# Net.net
KiCad netlist of a schematic drawn in Altium Designer
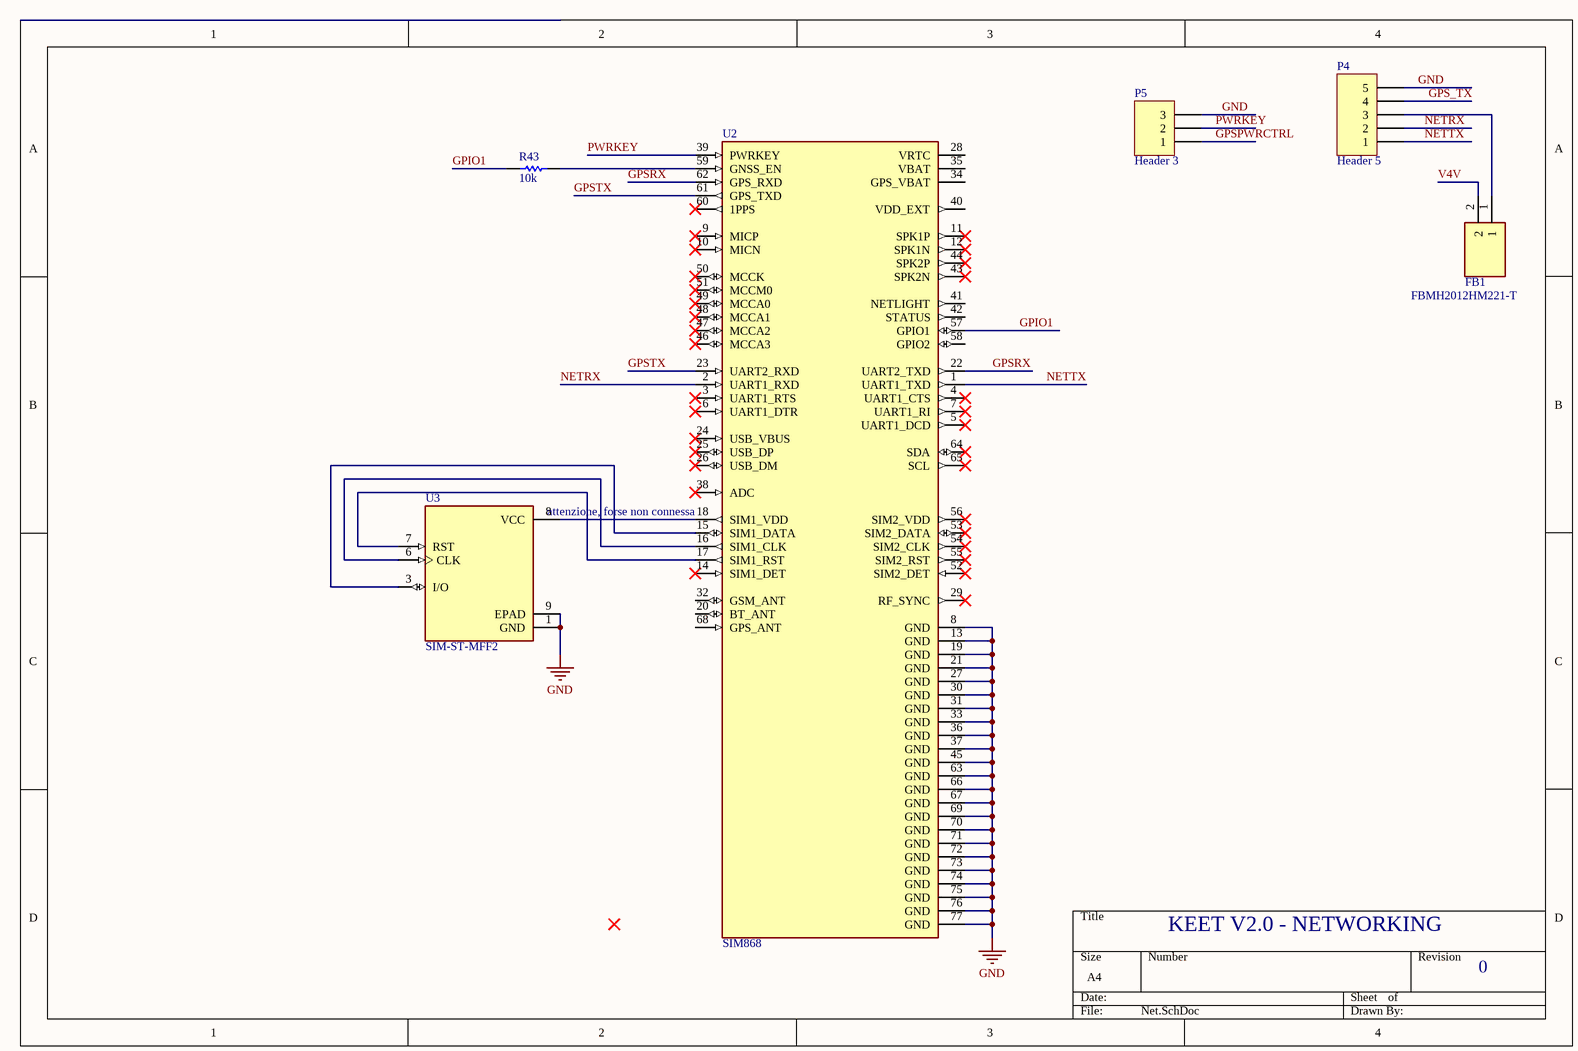
[diagram p0: Net.SchDoc]

(export (version "E")
  (design (tool "Eeschema 10.0.6"))
  (components
    (comp (ref "FB1")
      (value "FBMH2012HM221-T")
      (footprint "SamacSys:BEADC2012X105N")
      (description "Ferrite Bead")
      (fields (field (name "MOUSER PART NUMBER") "963-FBMH2012HM221-T"))
      (libsource (lib "*") (part "FBMH2012HM221-T"))
    )
    (comp (ref "P4")
      (value "Header 5")
      (footprint "HDR1X5")
      (description "Header, 5-Pin")
      (fields (field (name "PUBLISHER") "Altium Limited"))
      (libsource (lib "Miscellaneous Connectors") (part "Header 5"))
    )
    (comp (ref "P5")
      (value "Header 3")
      (footprint "HDR1X3")
      (description "Header, 3-Pin")
      (fields (field (name "PUBLISHER") "Altium Limited"))
      (libsource (lib "Miscellaneous Connectors") (part "Header 3"))
    )
    (comp (ref "R43")
      (value "10k")
      (footprint "RESC1005X04N")
      (description "Res Thick Film 0402 10K Ohm 1% 1/16W ±100ppm/°C Molded SMD Paper T/R")
      (fields
        (field (name "MANUFACTURER") "Vishay")
        (field (name "MANUFACTURER PART NUMBER") "CRCW0402-10K0FKED")
      )
      (libsource (lib "KeetV2") (part "CRCW0402-10K0FKED"))
    )
    (comp (ref "U2")
      (value "SIM868")
      (footprint "XCVR_SIM868")
      (description "SIM868 GNSS, GSM RF mikroBUSâ„¢ Clickâ„¢ Platform Evaluation Expansion Board")
      (fields (field (name "MF") "MikroElektronika"))
      (libsource (lib "SIM868") (part "SIM868"))
    )
    (comp (ref "U3")
      (value "SIM-ST-MFF2")
      (footprint "PSON127P500X600X82-9N")
      (description "GLOBAL IOT EMBEDDED SIM CHIP")
      (fields (field (name "MF") "Hologram, Inc."))
      (libsource (lib "SIM-ST-MFF2") (part "SIM-ST-MFF2"))
    )
  )
  (nets
    (net (code "1") (name "/GPIO1") (class "Default")
      (node (ref "R43") (pin "2") (pinfunction "2_2") (pintype "passive"))
      (node (ref "U2") (pin "57") (pinfunction "GPIO1_57") (pintype "bidirectional"))
    )
    (net (code "2") (name "/GPSPWRCTRL") (class "Default")
      (node (ref "P5") (pin "1") (pinfunction "1_1") (pintype "passive"))
    )
    (net (code "3") (name "/GPSRX") (class "Default")
      (node (ref "U2") (pin "22") (pinfunction "UART2_TXD_22") (pintype "output"))
      (node (ref "U2") (pin "62") (pinfunction "GPS_RXD_62") (pintype "input"))
    )
    (net (code "4") (name "/GPSTX") (class "Default")
      (node (ref "U2") (pin "23") (pinfunction "UART2_RXD_23") (pintype "input"))
      (node (ref "U2") (pin "61") (pinfunction "GPS_TXD_61") (pintype "output"))
    )
    (net (code "5") (name "/GPS_TX") (class "Default")
      (node (ref "P4") (pin "4") (pinfunction "4_4") (pintype "passive"))
    )
    (net (code "6") (name "/NETRX") (class "Default")
      (node (ref "P4") (pin "2") (pinfunction "2_2") (pintype "passive"))
      (node (ref "U2") (pin "2") (pinfunction "UART1_RXD_2") (pintype "input"))
    )
    (net (code "7") (name "/NETTX") (class "Default")
      (node (ref "P4") (pin "1") (pinfunction "1_1") (pintype "passive"))
      (node (ref "U2") (pin "1") (pinfunction "UART1_TXD_1") (pintype "output"))
    )
    (net (code "8") (name "/PWRKEY") (class "Default")
      (node (ref "P5") (pin "2") (pinfunction "2_2") (pintype "passive"))
      (node (ref "U2") (pin "39") (pinfunction "PWRKEY_39") (pintype "input"))
    )
    (net (code "9") (name "/V4V") (class "Default")
      (node (ref "FB1") (pin "2") (pinfunction "2_2") (pintype "passive"))
    )
    (net (code "10") (name "GND") (class "Default")
      (node (ref "P4") (pin "5") (pinfunction "5_5") (pintype "passive"))
      (node (ref "P5") (pin "3") (pinfunction "3_3") (pintype "passive"))
      (node (ref "U2") (pin "13") (pinfunction "GND_13") (pintype "power_in"))
      (node (ref "U2") (pin "19") (pinfunction "GND_19") (pintype "power_in"))
      (node (ref "U2") (pin "21") (pinfunction "GND_21") (pintype "power_in"))
      (node (ref "U2") (pin "27") (pinfunction "GND_27") (pintype "power_in"))
      (node (ref "U2") (pin "30") (pinfunction "GND_30") (pintype "power_in"))
      (node (ref "U2") (pin "31") (pinfunction "GND_31") (pintype "power_in"))
      (node (ref "U2") (pin "33") (pinfunction "GND_33") (pintype "power_in"))
      (node (ref "U2") (pin "36") (pinfunction "GND_36") (pintype "power_in"))
      (node (ref "U2") (pin "37") (pinfunction "GND_37") (pintype "power_in"))
      (node (ref "U2") (pin "45") (pinfunction "GND_45") (pintype "power_in"))
      (node (ref "U2") (pin "63") (pinfunction "GND_63") (pintype "power_in"))
      (node (ref "U2") (pin "66") (pinfunction "GND_66") (pintype "power_in"))
      (node (ref "U2") (pin "67") (pinfunction "GND_67") (pintype "power_in"))
      (node (ref "U2") (pin "69") (pinfunction "GND_69") (pintype "power_in"))
      (node (ref "U2") (pin "70") (pinfunction "GND_70") (pintype "power_in"))
      (node (ref "U2") (pin "71") (pinfunction "GND_71") (pintype "power_in"))
      (node (ref "U2") (pin "72") (pinfunction "GND_72") (pintype "power_in"))
      (node (ref "U2") (pin "73") (pinfunction "GND_73") (pintype "power_in"))
      (node (ref "U2") (pin "74") (pinfunction "GND_74") (pintype "power_in"))
      (node (ref "U2") (pin "75") (pinfunction "GND_75") (pintype "power_in"))
      (node (ref "U2") (pin "76") (pinfunction "GND_76") (pintype "power_in"))
      (node (ref "U2") (pin "77") (pinfunction "GND_77") (pintype "power_in"))
      (node (ref "U2") (pin "8") (pinfunction "GND_8") (pintype "power_in"))
      (node (ref "U3") (pin "1") (pinfunction "GND_1") (pintype "power_in"))
      (node (ref "U3") (pin "9") (pinfunction "EPAD_9") (pintype "passive"))
    )
    (net (code "11") (name "Net-(FB1-Pad1)") (class "Default")
      (node (ref "FB1") (pin "1") (pinfunction "1_1") (pintype "passive"))
      (node (ref "P4") (pin "3") (pinfunction "3_3") (pintype "passive"))
    )
    (net (code "12") (name "Net-(U2-GNSS_EN)") (class "Default")
      (node (ref "R43") (pin "1") (pinfunction "1_1") (pintype "passive"))
      (node (ref "U2") (pin "59") (pinfunction "GNSS_EN_59") (pintype "input"))
    )
    (net (code "13") (name "Net-(U2-SIM1_CLK)") (class "Default")
      (node (ref "U2") (pin "16") (pinfunction "SIM1_CLK_16") (pintype "output"))
      (node (ref "U3") (pin "6") (pinfunction "CLK_6") (pintype "input"))
    )
    (net (code "14") (name "Net-(U2-SIM1_DATA)") (class "Default")
      (node (ref "U2") (pin "15") (pinfunction "SIM1_DATA_15") (pintype "bidirectional"))
      (node (ref "U3") (pin "3") (pinfunction "I/O_3") (pintype "bidirectional"))
    )
    (net (code "15") (name "Net-(U2-SIM1_RST)") (class "Default")
      (node (ref "U2") (pin "17") (pinfunction "SIM1_RST_17") (pintype "output"))
      (node (ref "U3") (pin "7") (pinfunction "RST_7") (pintype "input"))
    )
    (net (code "16") (name "Net-(U2-SIM1_VDD)") (class "Default")
      (node (ref "U2") (pin "18") (pinfunction "SIM1_VDD_18") (pintype "output"))
      (node (ref "U3") (pin "8") (pinfunction "VCC_8") (pintype "power_in"))
    )
    (net (code "17") (name "unconnected-(U2-1PPS-Pad60)") (class "Default")
      (node (ref "U2") (pin "60") (pinfunction "1PPS_60") (pintype "output+no_connect"))
    )
    (net (code "18") (name "unconnected-(U2-ADC-Pad38)") (class "Default")
      (node (ref "U2") (pin "38") (pinfunction "ADC_38") (pintype "input+no_connect"))
    )
    (net (code "19") (name "unconnected-(U2-BT_ANT-Pad20)") (class "Default")
      (node (ref "U2") (pin "20") (pinfunction "BT_ANT_20") (pintype "bidirectional"))
    )
    (net (code "20") (name "unconnected-(U2-GPIO2-Pad58)") (class "Default")
      (node (ref "U2") (pin "58") (pinfunction "GPIO2_58") (pintype "bidirectional"))
    )
    (net (code "21") (name "unconnected-(U2-GPS_ANT-Pad68)") (class "Default")
      (node (ref "U2") (pin "68") (pinfunction "GPS_ANT_68") (pintype "input"))
    )
    (net (code "22") (name "unconnected-(U2-GPS_VBAT-Pad34)") (class "Default")
      (node (ref "U2") (pin "34") (pinfunction "GPS_VBAT_34") (pintype "power_in"))
    )
    (net (code "23") (name "unconnected-(U2-GSM_ANT-Pad32)") (class "Default")
      (node (ref "U2") (pin "32") (pinfunction "GSM_ANT_32") (pintype "bidirectional"))
    )
    (net (code "24") (name "unconnected-(U2-MCCA0-Pad49)") (class "Default")
      (node (ref "U2") (pin "49") (pinfunction "MCCA0_49") (pintype "bidirectional+no_connect"))
    )
    (net (code "25") (name "unconnected-(U2-MCCA1-Pad48)") (class "Default")
      (node (ref "U2") (pin "48") (pinfunction "MCCA1_48") (pintype "bidirectional+no_connect"))
    )
    (net (code "26") (name "unconnected-(U2-MCCA2-Pad47)") (class "Default")
      (node (ref "U2") (pin "47") (pinfunction "MCCA2_47") (pintype "bidirectional+no_connect"))
    )
    (net (code "27") (name "unconnected-(U2-MCCA3-Pad46)") (class "Default")
      (node (ref "U2") (pin "46") (pinfunction "MCCA3_46") (pintype "bidirectional+no_connect"))
    )
    (net (code "28") (name "unconnected-(U2-MCCK-Pad50)") (class "Default")
      (node (ref "U2") (pin "50") (pinfunction "MCCK_50") (pintype "bidirectional+no_connect"))
    )
    (net (code "29") (name "unconnected-(U2-MCCM0-Pad51)") (class "Default")
      (node (ref "U2") (pin "51") (pinfunction "MCCM0_51") (pintype "bidirectional+no_connect"))
    )
    (net (code "30") (name "unconnected-(U2-MICN-Pad10)") (class "Default")
      (node (ref "U2") (pin "10") (pinfunction "MICN_10") (pintype "input+no_connect"))
    )
    (net (code "31") (name "unconnected-(U2-MICP-Pad9)") (class "Default")
      (node (ref "U2") (pin "9") (pinfunction "MICP_9") (pintype "input+no_connect"))
    )
    (net (code "32") (name "unconnected-(U2-NETLIGHT-Pad41)") (class "Default")
      (node (ref "U2") (pin "41") (pinfunction "NETLIGHT_41") (pintype "output"))
    )
    (net (code "33") (name "unconnected-(U2-RF_SYNC-Pad29)") (class "Default")
      (node (ref "U2") (pin "29") (pinfunction "RF_SYNC_29") (pintype "output+no_connect"))
    )
    (net (code "34") (name "unconnected-(U2-SCL-Pad65)") (class "Default")
      (node (ref "U2") (pin "65") (pinfunction "SCL_65") (pintype "output+no_connect"))
    )
    (net (code "35") (name "unconnected-(U2-SDA-Pad64)") (class "Default")
      (node (ref "U2") (pin "64") (pinfunction "SDA_64") (pintype "bidirectional+no_connect"))
    )
    (net (code "36") (name "unconnected-(U2-SIM1_DET-Pad14)") (class "Default")
      (node (ref "U2") (pin "14") (pinfunction "SIM1_DET_14") (pintype "input+no_connect"))
    )
    (net (code "37") (name "unconnected-(U2-SIM2_CLK-Pad54)") (class "Default")
      (node (ref "U2") (pin "54") (pinfunction "SIM2_CLK_54") (pintype "output+no_connect"))
    )
    (net (code "38") (name "unconnected-(U2-SIM2_DATA-Pad53)") (class "Default")
      (node (ref "U2") (pin "53") (pinfunction "SIM2_DATA_53") (pintype "bidirectional+no_connect"))
    )
    (net (code "39") (name "unconnected-(U2-SIM2_DET-Pad52)") (class "Default")
      (node (ref "U2") (pin "52") (pinfunction "SIM2_DET_52") (pintype "input+no_connect"))
    )
    (net (code "40") (name "unconnected-(U2-SIM2_RST-Pad55)") (class "Default")
      (node (ref "U2") (pin "55") (pinfunction "SIM2_RST_55") (pintype "output+no_connect"))
    )
    (net (code "41") (name "unconnected-(U2-SIM2_VDD-Pad56)") (class "Default")
      (node (ref "U2") (pin "56") (pinfunction "SIM2_VDD_56") (pintype "output+no_connect"))
    )
    (net (code "42") (name "unconnected-(U2-SPK1N-Pad12)") (class "Default")
      (node (ref "U2") (pin "12") (pinfunction "SPK1N_12") (pintype "output+no_connect"))
    )
    (net (code "43") (name "unconnected-(U2-SPK1P-Pad11)") (class "Default")
      (node (ref "U2") (pin "11") (pinfunction "SPK1P_11") (pintype "output+no_connect"))
    )
    (net (code "44") (name "unconnected-(U2-SPK2N-Pad43)") (class "Default")
      (node (ref "U2") (pin "43") (pinfunction "SPK2N_43") (pintype "output+no_connect"))
    )
    (net (code "45") (name "unconnected-(U2-SPK2P-Pad44)") (class "Default")
      (node (ref "U2") (pin "44") (pinfunction "SPK2P_44") (pintype "output+no_connect"))
    )
    (net (code "46") (name "unconnected-(U2-STATUS-Pad42)") (class "Default")
      (node (ref "U2") (pin "42") (pinfunction "STATUS_42") (pintype "output"))
    )
    (net (code "47") (name "unconnected-(U2-UART1_CTS-Pad4)") (class "Default")
      (node (ref "U2") (pin "4") (pinfunction "UART1_CTS_4") (pintype "output+no_connect"))
    )
    (net (code "48") (name "unconnected-(U2-UART1_DCD-Pad5)") (class "Default")
      (node (ref "U2") (pin "5") (pinfunction "UART1_DCD_5") (pintype "output+no_connect"))
    )
    (net (code "49") (name "unconnected-(U2-UART1_DTR-Pad6)") (class "Default")
      (node (ref "U2") (pin "6") (pinfunction "UART1_DTR_6") (pintype "input+no_connect"))
    )
    (net (code "50") (name "unconnected-(U2-UART1_RI-Pad7)") (class "Default")
      (node (ref "U2") (pin "7") (pinfunction "UART1_RI_7") (pintype "output+no_connect"))
    )
    (net (code "51") (name "unconnected-(U2-UART1_RTS-Pad3)") (class "Default")
      (node (ref "U2") (pin "3") (pinfunction "UART1_RTS_3") (pintype "input+no_connect"))
    )
    (net (code "52") (name "unconnected-(U2-USB_DM-Pad26)") (class "Default")
      (node (ref "U2") (pin "26") (pinfunction "USB_DM_26") (pintype "bidirectional+no_connect"))
    )
    (net (code "53") (name "unconnected-(U2-USB_DP-Pad25)") (class "Default")
      (node (ref "U2") (pin "25") (pinfunction "USB_DP_25") (pintype "bidirectional+no_connect"))
    )
    (net (code "54") (name "unconnected-(U2-USB_VBUS-Pad24)") (class "Default")
      (node (ref "U2") (pin "24") (pinfunction "USB_VBUS_24") (pintype "input+no_connect"))
    )
    (net (code "55") (name "unconnected-(U2-VBAT-Pad35)") (class "Default")
      (node (ref "U2") (pin "35") (pinfunction "VBAT_35") (pintype "power_in"))
    )
    (net (code "56") (name "unconnected-(U2-VDD_EXT-Pad40)") (class "Default")
      (node (ref "U2") (pin "40") (pinfunction "VDD_EXT_40") (pintype "output"))
    )
    (net (code "57") (name "unconnected-(U2-VRTC-Pad28)") (class "Default")
      (node (ref "U2") (pin "28") (pinfunction "VRTC_28") (pintype "power_in"))
    )
  )
)
